# Limit_Switches.net
KiCad netlist of a schematic drawn in Altium Designer
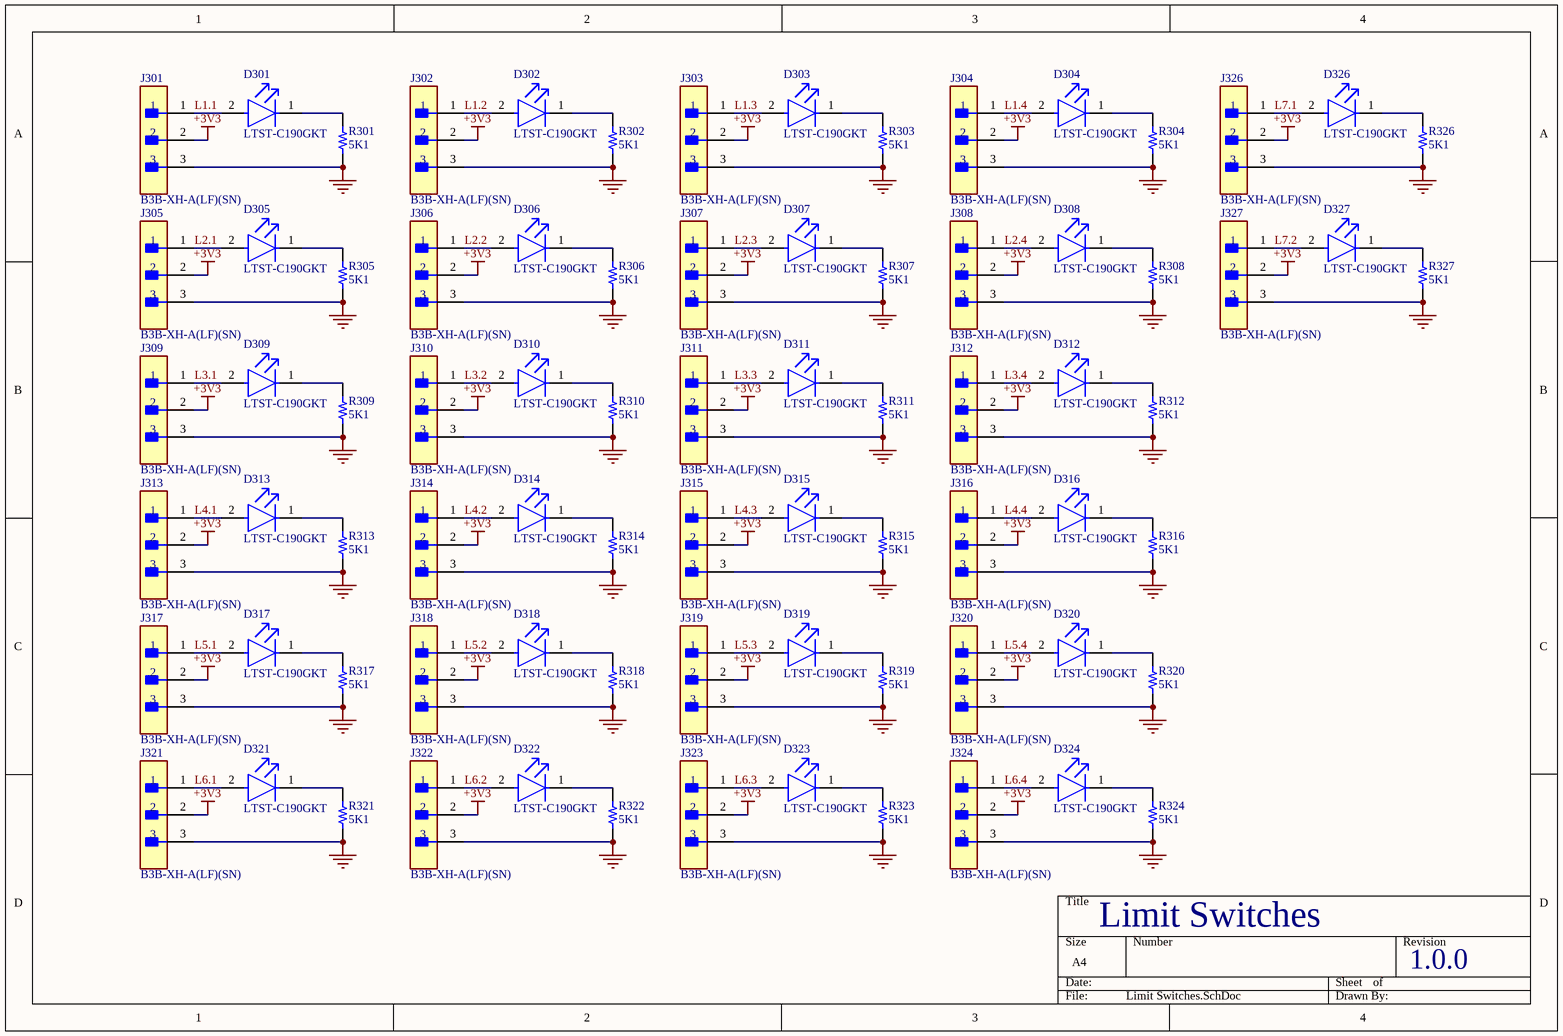
[diagram p0: Limit Switches.SchDoc]

(export (version "E")
  (design (tool "Eeschema 10.0.6"))
  (components
    (comp (ref "D301")
      (value "LTST-C190GKT")
      (footprint "FP-LTST-C190GKT-MFG")
      (description "LED GREEN CLEAR CHIP SMD")
      (fields (field (name "VOLTAGE") "2V"))
      (libsource (lib "Altium Content Vault") (part "8706943c75ba83719d021d2fdc84c58"))
    )
    (comp (ref "D302")
      (value "LTST-C190GKT")
      (footprint "FP-LTST-C190GKT-MFG")
      (description "LED GREEN CLEAR CHIP SMD")
      (fields (field (name "VOLTAGE") "2V"))
      (libsource (lib "Altium Content Vault") (part "8706943c75ba83719d021d2fdc84c58"))
    )
    (comp (ref "D303")
      (value "LTST-C190GKT")
      (footprint "FP-LTST-C190GKT-MFG")
      (description "LED GREEN CLEAR CHIP SMD")
      (fields (field (name "VOLTAGE") "2V"))
      (libsource (lib "Altium Content Vault") (part "8706943c75ba83719d021d2fdc84c58"))
    )
    (comp (ref "D304")
      (value "LTST-C190GKT")
      (footprint "FP-LTST-C190GKT-MFG")
      (description "LED GREEN CLEAR CHIP SMD")
      (fields (field (name "VOLTAGE") "2V"))
      (libsource (lib "Altium Content Vault") (part "8706943c75ba83719d021d2fdc84c58"))
    )
    (comp (ref "D305")
      (value "LTST-C190GKT")
      (footprint "FP-LTST-C190GKT-MFG")
      (description "LED GREEN CLEAR CHIP SMD")
      (fields (field (name "VOLTAGE") "2V"))
      (libsource (lib "Altium Content Vault") (part "8706943c75ba83719d021d2fdc84c58"))
    )
    (comp (ref "D306")
      (value "LTST-C190GKT")
      (footprint "FP-LTST-C190GKT-MFG")
      (description "LED GREEN CLEAR CHIP SMD")
      (fields (field (name "VOLTAGE") "2V"))
      (libsource (lib "Altium Content Vault") (part "8706943c75ba83719d021d2fdc84c58"))
    )
    (comp (ref "D307")
      (value "LTST-C190GKT")
      (footprint "FP-LTST-C190GKT-MFG")
      (description "LED GREEN CLEAR CHIP SMD")
      (fields (field (name "VOLTAGE") "2V"))
      (libsource (lib "Altium Content Vault") (part "8706943c75ba83719d021d2fdc84c58"))
    )
    (comp (ref "D308")
      (value "LTST-C190GKT")
      (footprint "FP-LTST-C190GKT-MFG")
      (description "LED GREEN CLEAR CHIP SMD")
      (fields (field (name "VOLTAGE") "2V"))
      (libsource (lib "Altium Content Vault") (part "8706943c75ba83719d021d2fdc84c58"))
    )
    (comp (ref "D309")
      (value "LTST-C190GKT")
      (footprint "FP-LTST-C190GKT-MFG")
      (description "LED GREEN CLEAR CHIP SMD")
      (fields (field (name "VOLTAGE") "2V"))
      (libsource (lib "Altium Content Vault") (part "8706943c75ba83719d021d2fdc84c58"))
    )
    (comp (ref "D310")
      (value "LTST-C190GKT")
      (footprint "FP-LTST-C190GKT-MFG")
      (description "LED GREEN CLEAR CHIP SMD")
      (fields (field (name "VOLTAGE") "2V"))
      (libsource (lib "Altium Content Vault") (part "8706943c75ba83719d021d2fdc84c58"))
    )
    (comp (ref "D311")
      (value "LTST-C190GKT")
      (footprint "FP-LTST-C190GKT-MFG")
      (description "LED GREEN CLEAR CHIP SMD")
      (fields (field (name "VOLTAGE") "2V"))
      (libsource (lib "Altium Content Vault") (part "8706943c75ba83719d021d2fdc84c58"))
    )
    (comp (ref "D312")
      (value "LTST-C190GKT")
      (footprint "FP-LTST-C190GKT-MFG")
      (description "LED GREEN CLEAR CHIP SMD")
      (fields (field (name "VOLTAGE") "2V"))
      (libsource (lib "Altium Content Vault") (part "8706943c75ba83719d021d2fdc84c58"))
    )
    (comp (ref "D313")
      (value "LTST-C190GKT")
      (footprint "FP-LTST-C190GKT-MFG")
      (description "LED GREEN CLEAR CHIP SMD")
      (fields (field (name "VOLTAGE") "2V"))
      (libsource (lib "Altium Content Vault") (part "8706943c75ba83719d021d2fdc84c58"))
    )
    (comp (ref "D314")
      (value "LTST-C190GKT")
      (footprint "FP-LTST-C190GKT-MFG")
      (description "LED GREEN CLEAR CHIP SMD")
      (fields (field (name "VOLTAGE") "2V"))
      (libsource (lib "Altium Content Vault") (part "8706943c75ba83719d021d2fdc84c58"))
    )
    (comp (ref "D315")
      (value "LTST-C190GKT")
      (footprint "FP-LTST-C190GKT-MFG")
      (description "LED GREEN CLEAR CHIP SMD")
      (fields (field (name "VOLTAGE") "2V"))
      (libsource (lib "Altium Content Vault") (part "8706943c75ba83719d021d2fdc84c58"))
    )
    (comp (ref "D316")
      (value "LTST-C190GKT")
      (footprint "FP-LTST-C190GKT-MFG")
      (description "LED GREEN CLEAR CHIP SMD")
      (fields (field (name "VOLTAGE") "2V"))
      (libsource (lib "Altium Content Vault") (part "8706943c75ba83719d021d2fdc84c58"))
    )
    (comp (ref "D317")
      (value "LTST-C190GKT")
      (footprint "FP-LTST-C190GKT-MFG")
      (description "LED GREEN CLEAR CHIP SMD")
      (fields (field (name "VOLTAGE") "2V"))
      (libsource (lib "Altium Content Vault") (part "8706943c75ba83719d021d2fdc84c58"))
    )
    (comp (ref "D318")
      (value "LTST-C190GKT")
      (footprint "FP-LTST-C190GKT-MFG")
      (description "LED GREEN CLEAR CHIP SMD")
      (fields (field (name "VOLTAGE") "2V"))
      (libsource (lib "Altium Content Vault") (part "8706943c75ba83719d021d2fdc84c58"))
    )
    (comp (ref "D319")
      (value "LTST-C190GKT")
      (footprint "FP-LTST-C190GKT-MFG")
      (description "LED GREEN CLEAR CHIP SMD")
      (fields (field (name "VOLTAGE") "2V"))
      (libsource (lib "Altium Content Vault") (part "8706943c75ba83719d021d2fdc84c58"))
    )
    (comp (ref "D320")
      (value "LTST-C190GKT")
      (footprint "FP-LTST-C190GKT-MFG")
      (description "LED GREEN CLEAR CHIP SMD")
      (fields (field (name "VOLTAGE") "2V"))
      (libsource (lib "Altium Content Vault") (part "8706943c75ba83719d021d2fdc84c58"))
    )
    (comp (ref "D321")
      (value "LTST-C190GKT")
      (footprint "FP-LTST-C190GKT-MFG")
      (description "LED GREEN CLEAR CHIP SMD")
      (fields (field (name "VOLTAGE") "2V"))
      (libsource (lib "Altium Content Vault") (part "8706943c75ba83719d021d2fdc84c58"))
    )
    (comp (ref "D322")
      (value "LTST-C190GKT")
      (footprint "FP-LTST-C190GKT-MFG")
      (description "LED GREEN CLEAR CHIP SMD")
      (fields (field (name "VOLTAGE") "2V"))
      (libsource (lib "Altium Content Vault") (part "8706943c75ba83719d021d2fdc84c58"))
    )
    (comp (ref "D323")
      (value "LTST-C190GKT")
      (footprint "FP-LTST-C190GKT-MFG")
      (description "LED GREEN CLEAR CHIP SMD")
      (fields (field (name "VOLTAGE") "2V"))
      (libsource (lib "Altium Content Vault") (part "8706943c75ba83719d021d2fdc84c58"))
    )
    (comp (ref "D324")
      (value "LTST-C190GKT")
      (footprint "FP-LTST-C190GKT-MFG")
      (description "LED GREEN CLEAR CHIP SMD")
      (fields (field (name "VOLTAGE") "2V"))
      (libsource (lib "Altium Content Vault") (part "8706943c75ba83719d021d2fdc84c58"))
    )
    (comp (ref "D326")
      (value "LTST-C190GKT")
      (footprint "FP-LTST-C190GKT-MFG")
      (description "LED GREEN CLEAR CHIP SMD")
      (fields (field (name "VOLTAGE") "2V"))
      (libsource (lib "Altium Content Vault") (part "8706943c75ba83719d021d2fdc84c58"))
    )
    (comp (ref "D327")
      (value "LTST-C190GKT")
      (footprint "FP-LTST-C190GKT-MFG")
      (description "LED GREEN CLEAR CHIP SMD")
      (fields (field (name "VOLTAGE") "2V"))
      (libsource (lib "Altium Content Vault") (part "8706943c75ba83719d021d2fdc84c58"))
    )
    (comp (ref "J301")
      (value "B3B-XH-A(LF)(SN)")
      (footprint "FP-B3B-XH-A_LF_SN-MFG")
      (description "CONN HEADER VERT 3POS 2.5MM")
      (libsource (lib "Altium Content Vault") (part "0d3f023dd272f625e17a2be33dea85f"))
    )
    (comp (ref "J302")
      (value "B3B-XH-A(LF)(SN)")
      (footprint "FP-B3B-XH-A_LF_SN-MFG")
      (description "CONN HEADER VERT 3POS 2.5MM")
      (libsource (lib "Altium Content Vault") (part "0d3f023dd272f625e17a2be33dea85f"))
    )
    (comp (ref "J303")
      (value "B3B-XH-A(LF)(SN)")
      (footprint "FP-B3B-XH-A_LF_SN-MFG")
      (description "CONN HEADER VERT 3POS 2.5MM")
      (libsource (lib "Altium Content Vault") (part "0d3f023dd272f625e17a2be33dea85f"))
    )
    (comp (ref "J304")
      (value "B3B-XH-A(LF)(SN)")
      (footprint "FP-B3B-XH-A_LF_SN-MFG")
      (description "CONN HEADER VERT 3POS 2.5MM")
      (libsource (lib "Altium Content Vault") (part "0d3f023dd272f625e17a2be33dea85f"))
    )
    (comp (ref "J305")
      (value "B3B-XH-A(LF)(SN)")
      (footprint "FP-B3B-XH-A_LF_SN-MFG")
      (description "CONN HEADER VERT 3POS 2.5MM")
      (libsource (lib "Altium Content Vault") (part "0d3f023dd272f625e17a2be33dea85f"))
    )
    (comp (ref "J306")
      (value "B3B-XH-A(LF)(SN)")
      (footprint "FP-B3B-XH-A_LF_SN-MFG")
      (description "CONN HEADER VERT 3POS 2.5MM")
      (libsource (lib "Altium Content Vault") (part "0d3f023dd272f625e17a2be33dea85f"))
    )
    (comp (ref "J307")
      (value "B3B-XH-A(LF)(SN)")
      (footprint "FP-B3B-XH-A_LF_SN-MFG")
      (description "CONN HEADER VERT 3POS 2.5MM")
      (libsource (lib "Altium Content Vault") (part "0d3f023dd272f625e17a2be33dea85f"))
    )
    (comp (ref "J308")
      (value "B3B-XH-A(LF)(SN)")
      (footprint "FP-B3B-XH-A_LF_SN-MFG")
      (description "CONN HEADER VERT 3POS 2.5MM")
      (libsource (lib "Altium Content Vault") (part "0d3f023dd272f625e17a2be33dea85f"))
    )
    (comp (ref "J309")
      (value "B3B-XH-A(LF)(SN)")
      (footprint "FP-B3B-XH-A_LF_SN-MFG")
      (description "CONN HEADER VERT 3POS 2.5MM")
      (libsource (lib "Altium Content Vault") (part "0d3f023dd272f625e17a2be33dea85f"))
    )
    (comp (ref "J310")
      (value "B3B-XH-A(LF)(SN)")
      (footprint "FP-B3B-XH-A_LF_SN-MFG")
      (description "CONN HEADER VERT 3POS 2.5MM")
      (libsource (lib "Altium Content Vault") (part "0d3f023dd272f625e17a2be33dea85f"))
    )
    (comp (ref "J311")
      (value "B3B-XH-A(LF)(SN)")
      (footprint "FP-B3B-XH-A_LF_SN-MFG")
      (description "CONN HEADER VERT 3POS 2.5MM")
      (libsource (lib "Altium Content Vault") (part "0d3f023dd272f625e17a2be33dea85f"))
    )
    (comp (ref "J312")
      (value "B3B-XH-A(LF)(SN)")
      (footprint "FP-B3B-XH-A_LF_SN-MFG")
      (description "CONN HEADER VERT 3POS 2.5MM")
      (libsource (lib "Altium Content Vault") (part "0d3f023dd272f625e17a2be33dea85f"))
    )
    (comp (ref "J313")
      (value "B3B-XH-A(LF)(SN)")
      (footprint "FP-B3B-XH-A_LF_SN-MFG")
      (description "CONN HEADER VERT 3POS 2.5MM")
      (libsource (lib "Altium Content Vault") (part "0d3f023dd272f625e17a2be33dea85f"))
    )
    (comp (ref "J314")
      (value "B3B-XH-A(LF)(SN)")
      (footprint "FP-B3B-XH-A_LF_SN-MFG")
      (description "CONN HEADER VERT 3POS 2.5MM")
      (libsource (lib "Altium Content Vault") (part "0d3f023dd272f625e17a2be33dea85f"))
    )
    (comp (ref "J315")
      (value "B3B-XH-A(LF)(SN)")
      (footprint "FP-B3B-XH-A_LF_SN-MFG")
      (description "CONN HEADER VERT 3POS 2.5MM")
      (libsource (lib "Altium Content Vault") (part "0d3f023dd272f625e17a2be33dea85f"))
    )
    (comp (ref "J316")
      (value "B3B-XH-A(LF)(SN)")
      (footprint "FP-B3B-XH-A_LF_SN-MFG")
      (description "CONN HEADER VERT 3POS 2.5MM")
      (libsource (lib "Altium Content Vault") (part "0d3f023dd272f625e17a2be33dea85f"))
    )
    (comp (ref "J317")
      (value "B3B-XH-A(LF)(SN)")
      (footprint "FP-B3B-XH-A_LF_SN-MFG")
      (description "CONN HEADER VERT 3POS 2.5MM")
      (libsource (lib "Altium Content Vault") (part "0d3f023dd272f625e17a2be33dea85f"))
    )
    (comp (ref "J318")
      (value "B3B-XH-A(LF)(SN)")
      (footprint "FP-B3B-XH-A_LF_SN-MFG")
      (description "CONN HEADER VERT 3POS 2.5MM")
      (libsource (lib "Altium Content Vault") (part "0d3f023dd272f625e17a2be33dea85f"))
    )
    (comp (ref "J319")
      (value "B3B-XH-A(LF)(SN)")
      (footprint "FP-B3B-XH-A_LF_SN-MFG")
      (description "CONN HEADER VERT 3POS 2.5MM")
      (libsource (lib "Altium Content Vault") (part "0d3f023dd272f625e17a2be33dea85f"))
    )
    (comp (ref "J320")
      (value "B3B-XH-A(LF)(SN)")
      (footprint "FP-B3B-XH-A_LF_SN-MFG")
      (description "CONN HEADER VERT 3POS 2.5MM")
      (libsource (lib "Altium Content Vault") (part "0d3f023dd272f625e17a2be33dea85f"))
    )
    (comp (ref "J321")
      (value "B3B-XH-A(LF)(SN)")
      (footprint "FP-B3B-XH-A_LF_SN-MFG")
      (description "CONN HEADER VERT 3POS 2.5MM")
      (libsource (lib "Altium Content Vault") (part "0d3f023dd272f625e17a2be33dea85f"))
    )
    (comp (ref "J322")
      (value "B3B-XH-A(LF)(SN)")
      (footprint "FP-B3B-XH-A_LF_SN-MFG")
      (description "CONN HEADER VERT 3POS 2.5MM")
      (libsource (lib "Altium Content Vault") (part "0d3f023dd272f625e17a2be33dea85f"))
    )
    (comp (ref "J323")
      (value "B3B-XH-A(LF)(SN)")
      (footprint "FP-B3B-XH-A_LF_SN-MFG")
      (description "CONN HEADER VERT 3POS 2.5MM")
      (libsource (lib "Altium Content Vault") (part "0d3f023dd272f625e17a2be33dea85f"))
    )
    (comp (ref "J324")
      (value "B3B-XH-A(LF)(SN)")
      (footprint "FP-B3B-XH-A_LF_SN-MFG")
      (description "CONN HEADER VERT 3POS 2.5MM")
      (libsource (lib "Altium Content Vault") (part "0d3f023dd272f625e17a2be33dea85f"))
    )
    (comp (ref "J326")
      (value "B3B-XH-A(LF)(SN)")
      (footprint "FP-B3B-XH-A_LF_SN-MFG")
      (description "CONN HEADER VERT 3POS 2.5MM")
      (libsource (lib "Altium Content Vault") (part "0d3f023dd272f625e17a2be33dea85f"))
    )
    (comp (ref "J327")
      (value "B3B-XH-A(LF)(SN)")
      (footprint "FP-B3B-XH-A_LF_SN-MFG")
      (description "CONN HEADER VERT 3POS 2.5MM")
      (libsource (lib "Altium Content Vault") (part "0d3f023dd272f625e17a2be33dea85f"))
    )
    (comp (ref "R301")
      (value "5K1")
      (footprint "RES 0402_1005")
      (description "RES SMD 5.1K OHM 5% 1/16W 0402")
      (fields (field (name "PART NUMBER") "AC0402JR-075K1L") (field (name "MANUFACTURER") "Yageo"))
      (libsource (lib "Celestial Altium Library - altium_library") (part "Resistor"))
    )
    (comp (ref "R302")
      (value "5K1")
      (footprint "RES 0402_1005")
      (description "RES SMD 5.1K OHM 5% 1/16W 0402")
      (fields (field (name "PART NUMBER") "AC0402JR-075K1L") (field (name "MANUFACTURER") "Yageo"))
      (libsource (lib "Celestial Altium Library - altium_library") (part "Resistor"))
    )
    (comp (ref "R303")
      (value "5K1")
      (footprint "RES 0402_1005")
      (description "RES SMD 5.1K OHM 5% 1/16W 0402")
      (fields (field (name "PART NUMBER") "AC0402JR-075K1L") (field (name "MANUFACTURER") "Yageo"))
      (libsource (lib "Celestial Altium Library - altium_library") (part "Resistor"))
    )
    (comp (ref "R304")
      (value "5K1")
      (footprint "RES 0402_1005")
      (description "RES SMD 5.1K OHM 5% 1/16W 0402")
      (fields (field (name "PART NUMBER") "AC0402JR-075K1L") (field (name "MANUFACTURER") "Yageo"))
      (libsource (lib "Celestial Altium Library - altium_library") (part "Resistor"))
    )
    (comp (ref "R305")
      (value "5K1")
      (footprint "RES 0402_1005")
      (description "RES SMD 5.1K OHM 5% 1/16W 0402")
      (fields (field (name "PART NUMBER") "AC0402JR-075K1L") (field (name "MANUFACTURER") "Yageo"))
      (libsource (lib "Celestial Altium Library - altium_library") (part "Resistor"))
    )
    (comp (ref "R306")
      (value "5K1")
      (footprint "RES 0402_1005")
      (description "RES SMD 5.1K OHM 5% 1/16W 0402")
      (fields (field (name "PART NUMBER") "AC0402JR-075K1L") (field (name "MANUFACTURER") "Yageo"))
      (libsource (lib "Celestial Altium Library - altium_library") (part "Resistor"))
    )
    (comp (ref "R307")
      (value "5K1")
      (footprint "RES 0402_1005")
      (description "RES SMD 5.1K OHM 5% 1/16W 0402")
      (fields (field (name "PART NUMBER") "AC0402JR-075K1L") (field (name "MANUFACTURER") "Yageo"))
      (libsource (lib "Celestial Altium Library - altium_library") (part "Resistor"))
    )
    (comp (ref "R308")
      (value "5K1")
      (footprint "RES 0402_1005")
      (description "RES SMD 5.1K OHM 5% 1/16W 0402")
      (fields (field (name "PART NUMBER") "AC0402JR-075K1L") (field (name "MANUFACTURER") "Yageo"))
      (libsource (lib "Celestial Altium Library - altium_library") (part "Resistor"))
    )
    (comp (ref "R309")
      (value "5K1")
      (footprint "RES 0402_1005")
      (description "RES SMD 5.1K OHM 5% 1/16W 0402")
      (fields (field (name "PART NUMBER") "AC0402JR-075K1L") (field (name "MANUFACTURER") "Yageo"))
      (libsource (lib "Celestial Altium Library - altium_library") (part "Resistor"))
    )
    (comp (ref "R310")
      (value "5K1")
      (footprint "RES 0402_1005")
      (description "RES SMD 5.1K OHM 5% 1/16W 0402")
      (fields (field (name "PART NUMBER") "AC0402JR-075K1L") (field (name "MANUFACTURER") "Yageo"))
      (libsource (lib "Celestial Altium Library - altium_library") (part "Resistor"))
    )
    (comp (ref "R311")
      (value "5K1")
      (footprint "RES 0402_1005")
      (description "RES SMD 5.1K OHM 5% 1/16W 0402")
      (fields (field (name "PART NUMBER") "AC0402JR-075K1L") (field (name "MANUFACTURER") "Yageo"))
      (libsource (lib "Celestial Altium Library - altium_library") (part "Resistor"))
    )
    (comp (ref "R312")
      (value "5K1")
      (footprint "RES 0402_1005")
      (description "RES SMD 5.1K OHM 5% 1/16W 0402")
      (fields (field (name "PART NUMBER") "AC0402JR-075K1L") (field (name "MANUFACTURER") "Yageo"))
      (libsource (lib "Celestial Altium Library - altium_library") (part "Resistor"))
    )
    (comp (ref "R313")
      (value "5K1")
      (footprint "RES 0402_1005")
      (description "RES SMD 5.1K OHM 5% 1/16W 0402")
      (fields (field (name "PART NUMBER") "AC0402JR-075K1L") (field (name "MANUFACTURER") "Yageo"))
      (libsource (lib "Celestial Altium Library - altium_library") (part "Resistor"))
    )
    (comp (ref "R314")
      (value "5K1")
      (footprint "RES 0402_1005")
      (description "RES SMD 5.1K OHM 5% 1/16W 0402")
      (fields (field (name "PART NUMBER") "AC0402JR-075K1L") (field (name "MANUFACTURER") "Yageo"))
      (libsource (lib "Celestial Altium Library - altium_library") (part "Resistor"))
    )
    (comp (ref "R315")
      (value "5K1")
      (footprint "RES 0402_1005")
      (description "RES SMD 5.1K OHM 5% 1/16W 0402")
      (fields (field (name "PART NUMBER") "AC0402JR-075K1L") (field (name "MANUFACTURER") "Yageo"))
      (libsource (lib "Celestial Altium Library - altium_library") (part "Resistor"))
    )
    (comp (ref "R316")
      (value "5K1")
      (footprint "RES 0402_1005")
      (description "RES SMD 5.1K OHM 5% 1/16W 0402")
      (fields (field (name "PART NUMBER") "AC0402JR-075K1L") (field (name "MANUFACTURER") "Yageo"))
      (libsource (lib "Celestial Altium Library - altium_library") (part "Resistor"))
    )
    (comp (ref "R317")
      (value "5K1")
      (footprint "RES 0402_1005")
      (description "RES SMD 5.1K OHM 5% 1/16W 0402")
      (fields (field (name "PART NUMBER") "AC0402JR-075K1L") (field (name "MANUFACTURER") "Yageo"))
      (libsource (lib "Celestial Altium Library - altium_library") (part "Resistor"))
    )
    (comp (ref "R318")
      (value "5K1")
      (footprint "RES 0402_1005")
      (description "RES SMD 5.1K OHM 5% 1/16W 0402")
      (fields (field (name "PART NUMBER") "AC0402JR-075K1L") (field (name "MANUFACTURER") "Yageo"))
      (libsource (lib "Celestial Altium Library - altium_library") (part "Resistor"))
    )
    (comp (ref "R319")
      (value "5K1")
      (footprint "RES 0402_1005")
      (description "RES SMD 5.1K OHM 5% 1/16W 0402")
      (fields (field (name "PART NUMBER") "AC0402JR-075K1L") (field (name "MANUFACTURER") "Yageo"))
      (libsource (lib "Celestial Altium Library - altium_library") (part "Resistor"))
    )
    (comp (ref "R320")
      (value "5K1")
      (footprint "RES 0402_1005")
      (description "RES SMD 5.1K OHM 5% 1/16W 0402")
      (fields (field (name "PART NUMBER") "AC0402JR-075K1L") (field (name "MANUFACTURER") "Yageo"))
      (libsource (lib "Celestial Altium Library - altium_library") (part "Resistor"))
    )
    (comp (ref "R321")
      (value "5K1")
      (footprint "RES 0402_1005")
      (description "RES SMD 5.1K OHM 5% 1/16W 0402")
      (fields (field (name "PART NUMBER") "AC0402JR-075K1L") (field (name "MANUFACTURER") "Yageo"))
      (libsource (lib "Celestial Altium Library - altium_library") (part "Resistor"))
    )
    (comp (ref "R322")
      (value "5K1")
      (footprint "RES 0402_1005")
      (description "RES SMD 5.1K OHM 5% 1/16W 0402")
      (fields (field (name "PART NUMBER") "AC0402JR-075K1L") (field (name "MANUFACTURER") "Yageo"))
      (libsource (lib "Celestial Altium Library - altium_library") (part "Resistor"))
    )
    (comp (ref "R323")
      (value "5K1")
      (footprint "RES 0402_1005")
      (description "RES SMD 5.1K OHM 5% 1/16W 0402")
      (fields (field (name "PART NUMBER") "AC0402JR-075K1L") (field (name "MANUFACTURER") "Yageo"))
      (libsource (lib "Celestial Altium Library - altium_library") (part "Resistor"))
    )
    (comp (ref "R324")
      (value "5K1")
      (footprint "RES 0402_1005")
      (description "RES SMD 5.1K OHM 5% 1/16W 0402")
      (fields (field (name "PART NUMBER") "AC0402JR-075K1L") (field (name "MANUFACTURER") "Yageo"))
      (libsource (lib "Celestial Altium Library - altium_library") (part "Resistor"))
    )
    (comp (ref "R326")
      (value "5K1")
      (footprint "RES 0402_1005")
      (description "RES SMD 5.1K OHM 5% 1/16W 0402")
      (fields (field (name "PART NUMBER") "AC0402JR-075K1L") (field (name "MANUFACTURER") "Yageo"))
      (libsource (lib "Celestial Altium Library - altium_library") (part "Resistor"))
    )
    (comp (ref "R327")
      (value "5K1")
      (footprint "RES 0402_1005")
      (description "RES SMD 5.1K OHM 5% 1/16W 0402")
      (fields (field (name "PART NUMBER") "AC0402JR-075K1L") (field (name "MANUFACTURER") "Yageo"))
      (libsource (lib "Celestial Altium Library - altium_library") (part "Resistor"))
    )
  )
  (nets
    (net (code "1") (name "+3V3") (class "Default")
      (node (ref "J301") (pin "2") (pinfunction "2_2") (pintype "passive"))
      (node (ref "J302") (pin "2") (pinfunction "2_2") (pintype "passive"))
      (node (ref "J303") (pin "2") (pinfunction "2_2") (pintype "passive"))
      (node (ref "J304") (pin "2") (pinfunction "2_2") (pintype "passive"))
      (node (ref "J305") (pin "2") (pinfunction "2_2") (pintype "passive"))
      (node (ref "J306") (pin "2") (pinfunction "2_2") (pintype "passive"))
      (node (ref "J307") (pin "2") (pinfunction "2_2") (pintype "passive"))
      (node (ref "J308") (pin "2") (pinfunction "2_2") (pintype "passive"))
      (node (ref "J309") (pin "2") (pinfunction "2_2") (pintype "passive"))
      (node (ref "J310") (pin "2") (pinfunction "2_2") (pintype "passive"))
      (node (ref "J311") (pin "2") (pinfunction "2_2") (pintype "passive"))
      (node (ref "J312") (pin "2") (pinfunction "2_2") (pintype "passive"))
      (node (ref "J313") (pin "2") (pinfunction "2_2") (pintype "passive"))
      (node (ref "J314") (pin "2") (pinfunction "2_2") (pintype "passive"))
      (node (ref "J315") (pin "2") (pinfunction "2_2") (pintype "passive"))
      (node (ref "J316") (pin "2") (pinfunction "2_2") (pintype "passive"))
      (node (ref "J317") (pin "2") (pinfunction "2_2") (pintype "passive"))
      (node (ref "J318") (pin "2") (pinfunction "2_2") (pintype "passive"))
      (node (ref "J319") (pin "2") (pinfunction "2_2") (pintype "passive"))
      (node (ref "J320") (pin "2") (pinfunction "2_2") (pintype "passive"))
      (node (ref "J321") (pin "2") (pinfunction "2_2") (pintype "passive"))
      (node (ref "J322") (pin "2") (pinfunction "2_2") (pintype "passive"))
      (node (ref "J323") (pin "2") (pinfunction "2_2") (pintype "passive"))
      (node (ref "J324") (pin "2") (pinfunction "2_2") (pintype "passive"))
      (node (ref "J326") (pin "2") (pinfunction "2_2") (pintype "passive"))
      (node (ref "J327") (pin "2") (pinfunction "2_2") (pintype "passive"))
    )
    (net (code "2") (name "/L1.1") (class "Default")
      (node (ref "D301") (pin "2") (pinfunction "A_2") (pintype "passive"))
      (node (ref "J301") (pin "1") (pinfunction "1_1") (pintype "passive"))
    )
    (net (code "3") (name "/L1.2") (class "Default")
      (node (ref "D302") (pin "2") (pinfunction "A_2") (pintype "passive"))
      (node (ref "J302") (pin "1") (pinfunction "1_1") (pintype "passive"))
    )
    (net (code "4") (name "/L1.3") (class "Default")
      (node (ref "D303") (pin "2") (pinfunction "A_2") (pintype "passive"))
      (node (ref "J303") (pin "1") (pinfunction "1_1") (pintype "passive"))
    )
    (net (code "5") (name "/L1.4") (class "Default")
      (node (ref "D304") (pin "2") (pinfunction "A_2") (pintype "passive"))
      (node (ref "J304") (pin "1") (pinfunction "1_1") (pintype "passive"))
    )
    (net (code "6") (name "/L2.1") (class "Default")
      (node (ref "D305") (pin "2") (pinfunction "A_2") (pintype "passive"))
      (node (ref "J305") (pin "1") (pinfunction "1_1") (pintype "passive"))
    )
    (net (code "7") (name "/L2.2") (class "Default")
      (node (ref "D306") (pin "2") (pinfunction "A_2") (pintype "passive"))
      (node (ref "J306") (pin "1") (pinfunction "1_1") (pintype "passive"))
    )
    (net (code "8") (name "/L2.3") (class "Default")
      (node (ref "D307") (pin "2") (pinfunction "A_2") (pintype "passive"))
      (node (ref "J307") (pin "1") (pinfunction "1_1") (pintype "passive"))
    )
    (net (code "9") (name "/L2.4") (class "Default")
      (node (ref "D308") (pin "2") (pinfunction "A_2") (pintype "passive"))
      (node (ref "J308") (pin "1") (pinfunction "1_1") (pintype "passive"))
    )
    (net (code "10") (name "/L3.1") (class "Default")
      (node (ref "D309") (pin "2") (pinfunction "A_2") (pintype "passive"))
      (node (ref "J309") (pin "1") (pinfunction "1_1") (pintype "passive"))
    )
    (net (code "11") (name "/L3.2") (class "Default")
      (node (ref "D310") (pin "2") (pinfunction "A_2") (pintype "passive"))
      (node (ref "J310") (pin "1") (pinfunction "1_1") (pintype "passive"))
    )
    (net (code "12") (name "/L3.3") (class "Default")
      (node (ref "D311") (pin "2") (pinfunction "A_2") (pintype "passive"))
      (node (ref "J311") (pin "1") (pinfunction "1_1") (pintype "passive"))
    )
    (net (code "13") (name "/L3.4") (class "Default")
      (node (ref "D312") (pin "2") (pinfunction "A_2") (pintype "passive"))
      (node (ref "J312") (pin "1") (pinfunction "1_1") (pintype "passive"))
    )
    (net (code "14") (name "/L4.1") (class "Default")
      (node (ref "D313") (pin "2") (pinfunction "A_2") (pintype "passive"))
      (node (ref "J313") (pin "1") (pinfunction "1_1") (pintype "passive"))
    )
    (net (code "15") (name "/L4.2") (class "Default")
      (node (ref "D314") (pin "2") (pinfunction "A_2") (pintype "passive"))
      (node (ref "J314") (pin "1") (pinfunction "1_1") (pintype "passive"))
    )
    (net (code "16") (name "/L4.3") (class "Default")
      (node (ref "D315") (pin "2") (pinfunction "A_2") (pintype "passive"))
      (node (ref "J315") (pin "1") (pinfunction "1_1") (pintype "passive"))
    )
    (net (code "17") (name "/L4.4") (class "Default")
      (node (ref "D316") (pin "2") (pinfunction "A_2") (pintype "passive"))
      (node (ref "J316") (pin "1") (pinfunction "1_1") (pintype "passive"))
    )
    (net (code "18") (name "/L5.1") (class "Default")
      (node (ref "D317") (pin "2") (pinfunction "A_2") (pintype "passive"))
      (node (ref "J317") (pin "1") (pinfunction "1_1") (pintype "passive"))
    )
    (net (code "19") (name "/L5.2") (class "Default")
      (node (ref "D318") (pin "2") (pinfunction "A_2") (pintype "passive"))
      (node (ref "J318") (pin "1") (pinfunction "1_1") (pintype "passive"))
    )
    (net (code "20") (name "/L5.3") (class "Default")
      (node (ref "D319") (pin "2") (pinfunction "A_2") (pintype "passive"))
      (node (ref "J319") (pin "1") (pinfunction "1_1") (pintype "passive"))
    )
    (net (code "21") (name "/L5.4") (class "Default")
      (node (ref "D320") (pin "2") (pinfunction "A_2") (pintype "passive"))
      (node (ref "J320") (pin "1") (pinfunction "1_1") (pintype "passive"))
    )
    (net (code "22") (name "/L6.1") (class "Default")
      (node (ref "D321") (pin "2") (pinfunction "A_2") (pintype "passive"))
      (node (ref "J321") (pin "1") (pinfunction "1_1") (pintype "passive"))
    )
    (net (code "23") (name "/L6.2") (class "Default")
      (node (ref "D322") (pin "2") (pinfunction "A_2") (pintype "passive"))
      (node (ref "J322") (pin "1") (pinfunction "1_1") (pintype "passive"))
    )
    (net (code "24") (name "/L6.3") (class "Default")
      (node (ref "D323") (pin "2") (pinfunction "A_2") (pintype "passive"))
      (node (ref "J323") (pin "1") (pinfunction "1_1") (pintype "passive"))
    )
    (net (code "25") (name "/L6.4") (class "Default")
      (node (ref "D324") (pin "2") (pinfunction "A_2") (pintype "passive"))
      (node (ref "J324") (pin "1") (pinfunction "1_1") (pintype "passive"))
    )
    (net (code "26") (name "/L7.1") (class "Default")
      (node (ref "D326") (pin "2") (pinfunction "A_2") (pintype "passive"))
      (node (ref "J326") (pin "1") (pinfunction "1_1") (pintype "passive"))
    )
    (net (code "27") (name "/L7.2") (class "Default")
      (node (ref "D327") (pin "2") (pinfunction "A_2") (pintype "passive"))
      (node (ref "J327") (pin "1") (pinfunction "1_1") (pintype "passive"))
    )
    (net (code "28") (name "GND") (class "Default")
      (node (ref "J301") (pin "3") (pinfunction "3_3") (pintype "passive"))
      (node (ref "J302") (pin "3") (pinfunction "3_3") (pintype "passive"))
      (node (ref "J303") (pin "3") (pinfunction "3_3") (pintype "passive"))
      (node (ref "J304") (pin "3") (pinfunction "3_3") (pintype "passive"))
      (node (ref "J305") (pin "3") (pinfunction "3_3") (pintype "passive"))
      (node (ref "J306") (pin "3") (pinfunction "3_3") (pintype "passive"))
      (node (ref "J307") (pin "3") (pinfunction "3_3") (pintype "passive"))
      (node (ref "J308") (pin "3") (pinfunction "3_3") (pintype "passive"))
      (node (ref "J309") (pin "3") (pinfunction "3_3") (pintype "passive"))
      (node (ref "J310") (pin "3") (pinfunction "3_3") (pintype "passive"))
      (node (ref "J311") (pin "3") (pinfunction "3_3") (pintype "passive"))
      (node (ref "J312") (pin "3") (pinfunction "3_3") (pintype "passive"))
      (node (ref "J313") (pin "3") (pinfunction "3_3") (pintype "passive"))
      (node (ref "J314") (pin "3") (pinfunction "3_3") (pintype "passive"))
      (node (ref "J315") (pin "3") (pinfunction "3_3") (pintype "passive"))
      (node (ref "J316") (pin "3") (pinfunction "3_3") (pintype "passive"))
      (node (ref "J317") (pin "3") (pinfunction "3_3") (pintype "passive"))
      (node (ref "J318") (pin "3") (pinfunction "3_3") (pintype "passive"))
      (node (ref "J319") (pin "3") (pinfunction "3_3") (pintype "passive"))
      (node (ref "J320") (pin "3") (pinfunction "3_3") (pintype "passive"))
      (node (ref "J321") (pin "3") (pinfunction "3_3") (pintype "passive"))
      (node (ref "J322") (pin "3") (pinfunction "3_3") (pintype "passive"))
      (node (ref "J323") (pin "3") (pinfunction "3_3") (pintype "passive"))
      (node (ref "J324") (pin "3") (pinfunction "3_3") (pintype "passive"))
      (node (ref "J326") (pin "3") (pinfunction "3_3") (pintype "passive"))
      (node (ref "J327") (pin "3") (pinfunction "3_3") (pintype "passive"))
      (node (ref "R301") (pin "1") (pinfunction "1_1") (pintype "passive"))
      (node (ref "R302") (pin "1") (pinfunction "1_1") (pintype "passive"))
      (node (ref "R303") (pin "1") (pinfunction "1_1") (pintype "passive"))
      (node (ref "R304") (pin "1") (pinfunction "1_1") (pintype "passive"))
      (node (ref "R305") (pin "1") (pinfunction "1_1") (pintype "passive"))
      (node (ref "R306") (pin "1") (pinfunction "1_1") (pintype "passive"))
      (node (ref "R307") (pin "1") (pinfunction "1_1") (pintype "passive"))
      (node (ref "R308") (pin "1") (pinfunction "1_1") (pintype "passive"))
      (node (ref "R309") (pin "1") (pinfunction "1_1") (pintype "passive"))
      (node (ref "R310") (pin "1") (pinfunction "1_1") (pintype "passive"))
      (node (ref "R311") (pin "1") (pinfunction "1_1") (pintype "passive"))
      (node (ref "R312") (pin "1") (pinfunction "1_1") (pintype "passive"))
      (node (ref "R313") (pin "1") (pinfunction "1_1") (pintype "passive"))
      (node (ref "R314") (pin "1") (pinfunction "1_1") (pintype "passive"))
      (node (ref "R315") (pin "1") (pinfunction "1_1") (pintype "passive"))
      (node (ref "R316") (pin "1") (pinfunction "1_1") (pintype "passive"))
      (node (ref "R317") (pin "1") (pinfunction "1_1") (pintype "passive"))
      (node (ref "R318") (pin "1") (pinfunction "1_1") (pintype "passive"))
      (node (ref "R319") (pin "1") (pinfunction "1_1") (pintype "passive"))
      (node (ref "R320") (pin "1") (pinfunction "1_1") (pintype "passive"))
      (node (ref "R321") (pin "1") (pinfunction "1_1") (pintype "passive"))
      (node (ref "R322") (pin "1") (pinfunction "1_1") (pintype "passive"))
      (node (ref "R323") (pin "1") (pinfunction "1_1") (pintype "passive"))
      (node (ref "R324") (pin "1") (pinfunction "1_1") (pintype "passive"))
      (node (ref "R326") (pin "1") (pinfunction "1_1") (pintype "passive"))
      (node (ref "R327") (pin "1") (pinfunction "1_1") (pintype "passive"))
    )
    (net (code "29") (name "Net-(D301-C)") (class "Default")
      (node (ref "D301") (pin "1") (pinfunction "C_1") (pintype "passive"))
      (node (ref "R301") (pin "2") (pinfunction "2_2") (pintype "passive"))
    )
    (net (code "30") (name "Net-(D302-C)") (class "Default")
      (node (ref "D302") (pin "1") (pinfunction "C_1") (pintype "passive"))
      (node (ref "R302") (pin "2") (pinfunction "2_2") (pintype "passive"))
    )
    (net (code "31") (name "Net-(D303-C)") (class "Default")
      (node (ref "D303") (pin "1") (pinfunction "C_1") (pintype "passive"))
      (node (ref "R303") (pin "2") (pinfunction "2_2") (pintype "passive"))
    )
    (net (code "32") (name "Net-(D304-C)") (class "Default")
      (node (ref "D304") (pin "1") (pinfunction "C_1") (pintype "passive"))
      (node (ref "R304") (pin "2") (pinfunction "2_2") (pintype "passive"))
    )
    (net (code "33") (name "Net-(D305-C)") (class "Default")
      (node (ref "D305") (pin "1") (pinfunction "C_1") (pintype "passive"))
      (node (ref "R305") (pin "2") (pinfunction "2_2") (pintype "passive"))
    )
    (net (code "34") (name "Net-(D306-C)") (class "Default")
      (node (ref "D306") (pin "1") (pinfunction "C_1") (pintype "passive"))
      (node (ref "R306") (pin "2") (pinfunction "2_2") (pintype "passive"))
    )
    (net (code "35") (name "Net-(D307-C)") (class "Default")
      (node (ref "D307") (pin "1") (pinfunction "C_1") (pintype "passive"))
      (node (ref "R307") (pin "2") (pinfunction "2_2") (pintype "passive"))
    )
    (net (code "36") (name "Net-(D308-C)") (class "Default")
      (node (ref "D308") (pin "1") (pinfunction "C_1") (pintype "passive"))
      (node (ref "R308") (pin "2") (pinfunction "2_2") (pintype "passive"))
    )
    (net (code "37") (name "Net-(D309-C)") (class "Default")
      (node (ref "D309") (pin "1") (pinfunction "C_1") (pintype "passive"))
      (node (ref "R309") (pin "2") (pinfunction "2_2") (pintype "passive"))
    )
    (net (code "38") (name "Net-(D310-C)") (class "Default")
      (node (ref "D310") (pin "1") (pinfunction "C_1") (pintype "passive"))
      (node (ref "R310") (pin "2") (pinfunction "2_2") (pintype "passive"))
    )
    (net (code "39") (name "Net-(D311-C)") (class "Default")
      (node (ref "D311") (pin "1") (pinfunction "C_1") (pintype "passive"))
      (node (ref "R311") (pin "2") (pinfunction "2_2") (pintype "passive"))
    )
    (net (code "40") (name "Net-(D312-C)") (class "Default")
      (node (ref "D312") (pin "1") (pinfunction "C_1") (pintype "passive"))
      (node (ref "R312") (pin "2") (pinfunction "2_2") (pintype "passive"))
    )
    (net (code "41") (name "Net-(D313-C)") (class "Default")
      (node (ref "D313") (pin "1") (pinfunction "C_1") (pintype "passive"))
      (node (ref "R313") (pin "2") (pinfunction "2_2") (pintype "passive"))
    )
    (net (code "42") (name "Net-(D314-C)") (class "Default")
      (node (ref "D314") (pin "1") (pinfunction "C_1") (pintype "passive"))
      (node (ref "R314") (pin "2") (pinfunction "2_2") (pintype "passive"))
    )
    (net (code "43") (name "Net-(D315-C)") (class "Default")
      (node (ref "D315") (pin "1") (pinfunction "C_1") (pintype "passive"))
      (node (ref "R315") (pin "2") (pinfunction "2_2") (pintype "passive"))
    )
    (net (code "44") (name "Net-(D316-C)") (class "Default")
      (node (ref "D316") (pin "1") (pinfunction "C_1") (pintype "passive"))
      (node (ref "R316") (pin "2") (pinfunction "2_2") (pintype "passive"))
    )
    (net (code "45") (name "Net-(D317-C)") (class "Default")
      (node (ref "D317") (pin "1") (pinfunction "C_1") (pintype "passive"))
      (node (ref "R317") (pin "2") (pinfunction "2_2") (pintype "passive"))
    )
    (net (code "46") (name "Net-(D318-C)") (class "Default")
      (node (ref "D318") (pin "1") (pinfunction "C_1") (pintype "passive"))
      (node (ref "R318") (pin "2") (pinfunction "2_2") (pintype "passive"))
    )
    (net (code "47") (name "Net-(D319-C)") (class "Default")
      (node (ref "D319") (pin "1") (pinfunction "C_1") (pintype "passive"))
      (node (ref "R319") (pin "2") (pinfunction "2_2") (pintype "passive"))
    )
    (net (code "48") (name "Net-(D320-C)") (class "Default")
      (node (ref "D320") (pin "1") (pinfunction "C_1") (pintype "passive"))
      (node (ref "R320") (pin "2") (pinfunction "2_2") (pintype "passive"))
    )
    (net (code "49") (name "Net-(D321-C)") (class "Default")
      (node (ref "D321") (pin "1") (pinfunction "C_1") (pintype "passive"))
      (node (ref "R321") (pin "2") (pinfunction "2_2") (pintype "passive"))
    )
    (net (code "50") (name "Net-(D322-C)") (class "Default")
      (node (ref "D322") (pin "1") (pinfunction "C_1") (pintype "passive"))
      (node (ref "R322") (pin "2") (pinfunction "2_2") (pintype "passive"))
    )
    (net (code "51") (name "Net-(D323-C)") (class "Default")
      (node (ref "D323") (pin "1") (pinfunction "C_1") (pintype "passive"))
      (node (ref "R323") (pin "2") (pinfunction "2_2") (pintype "passive"))
    )
    (net (code "52") (name "Net-(D324-C)") (class "Default")
      (node (ref "D324") (pin "1") (pinfunction "C_1") (pintype "passive"))
      (node (ref "R324") (pin "2") (pinfunction "2_2") (pintype "passive"))
    )
    (net (code "53") (name "Net-(D326-C)") (class "Default")
      (node (ref "D326") (pin "1") (pinfunction "C_1") (pintype "passive"))
      (node (ref "R326") (pin "2") (pinfunction "2_2") (pintype "passive"))
    )
    (net (code "54") (name "Net-(D327-C)") (class "Default")
      (node (ref "D327") (pin "1") (pinfunction "C_1") (pintype "passive"))
      (node (ref "R327") (pin "2") (pinfunction "2_2") (pintype "passive"))
    )
  )
)
